# BPMLabLineRX21.net
KiCad netlist of a schematic drawn in EAGLE
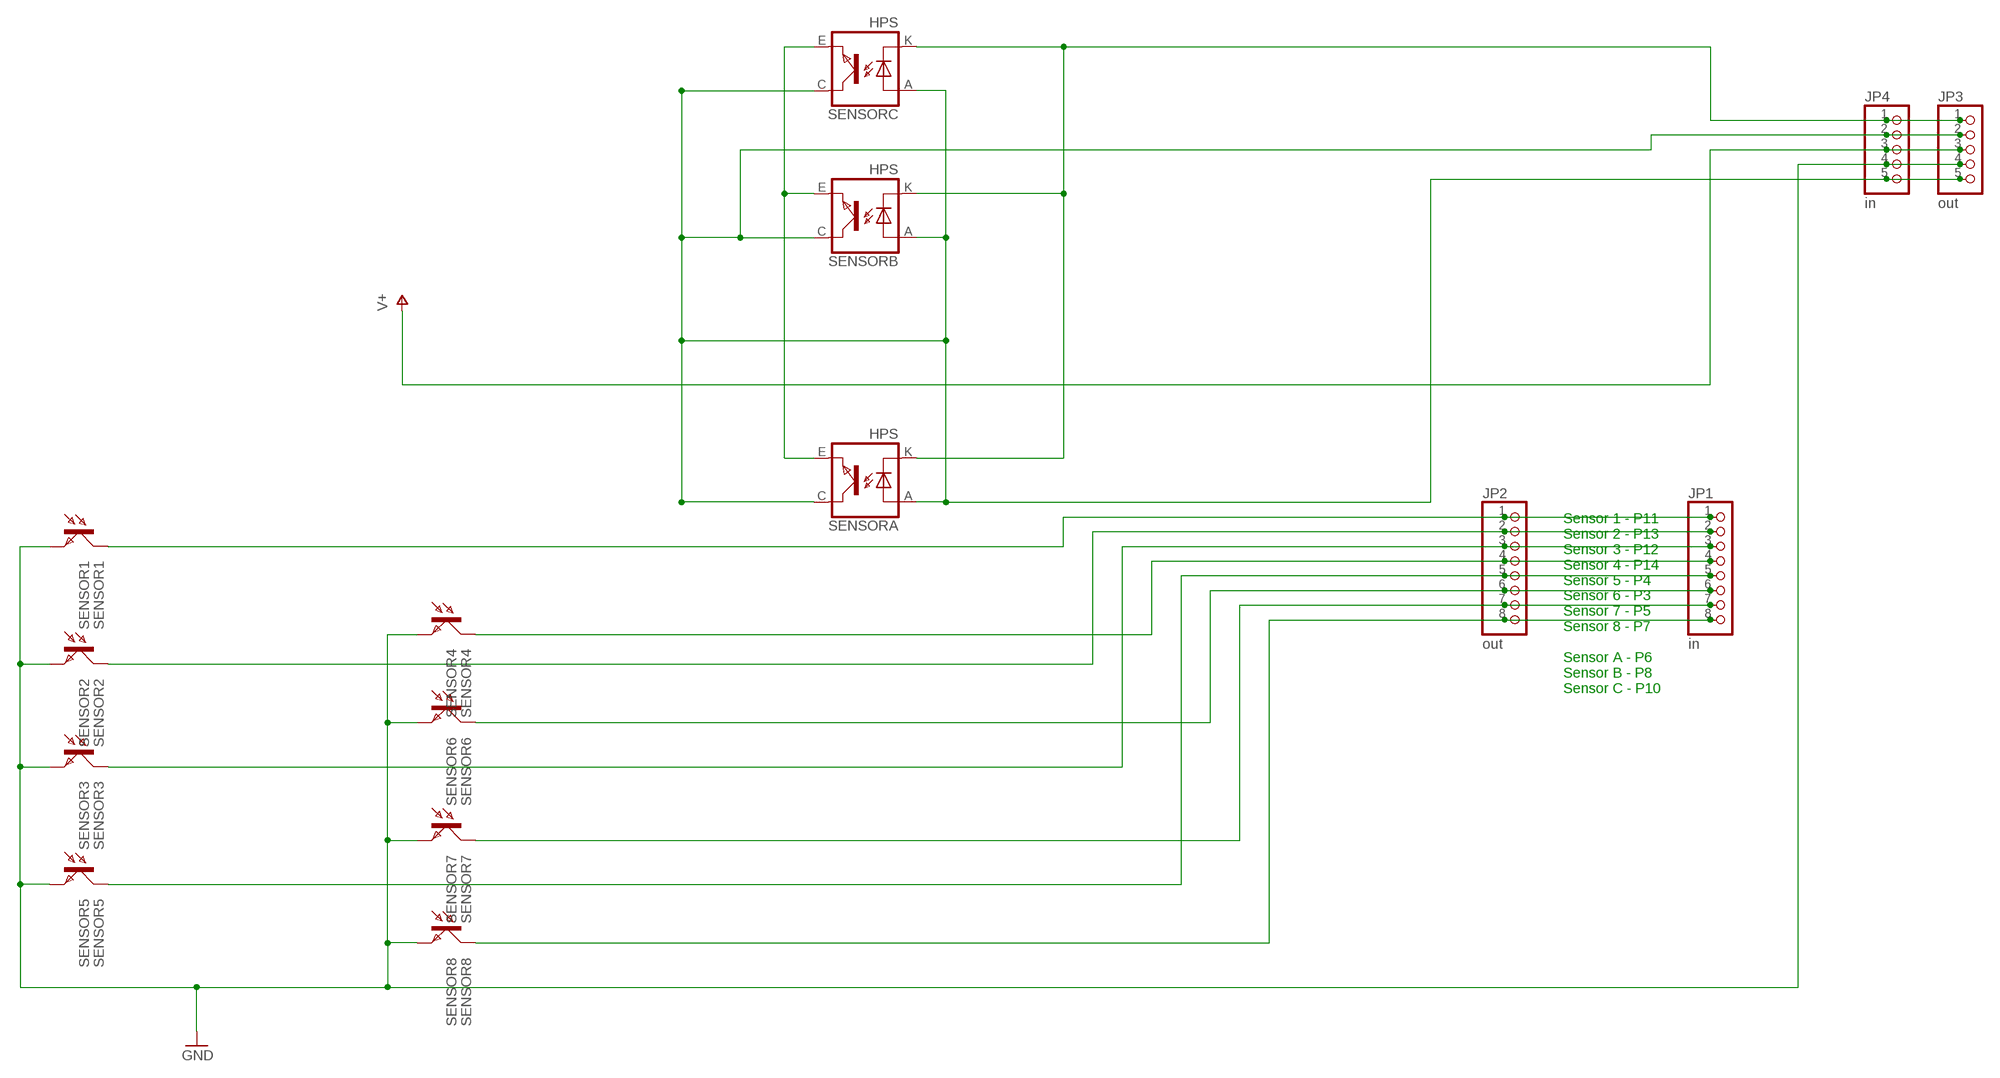
[diagram p0: schematic, sheet 1]

(export (version "E")
  (design (tool "Eeschema 10.0.6"))
  (components
    (comp (ref "JP1")
      (value "in")
      (footprint "eagle-import:1X08")
      (libsource (lib "eagle-import") (part "PINHD-1X8"))
    )
    (comp (ref "JP2")
      (value "out")
      (footprint "eagle-import:1X08")
      (libsource (lib "eagle-import") (part "PINHD-1X8"))
    )
    (comp (ref "JP3")
      (value "out")
      (footprint "eagle-import:1X05")
      (libsource (lib "eagle-import") (part "PINHD-1X5"))
    )
    (comp (ref "JP4")
      (value "in")
      (footprint "eagle-import:1X05")
      (libsource (lib "eagle-import") (part "PINHD-1X5"))
    )
    (comp (ref "SENSOR1")
      (value "SENSOR1")
      (footprint "eagle-import:BPX81")
      (libsource (lib "eagle-import") (part "BPX81"))
    )
    (comp (ref "SENSOR2")
      (value "SENSOR2")
      (footprint "eagle-import:BPX81")
      (libsource (lib "eagle-import") (part "BPX81"))
    )
    (comp (ref "SENSOR3")
      (value "SENSOR3")
      (footprint "eagle-import:BPX81")
      (libsource (lib "eagle-import") (part "BPX81"))
    )
    (comp (ref "SENSOR4")
      (value "SENSOR4")
      (footprint "eagle-import:BPX81")
      (libsource (lib "eagle-import") (part "BPX81"))
    )
    (comp (ref "SENSOR5")
      (value "SENSOR5")
      (footprint "eagle-import:BPX81")
      (libsource (lib "eagle-import") (part "BPX81"))
    )
    (comp (ref "SENSOR6")
      (value "SENSOR6")
      (footprint "eagle-import:BPX81")
      (libsource (lib "eagle-import") (part "BPX81"))
    )
    (comp (ref "SENSOR7")
      (value "SENSOR7")
      (footprint "eagle-import:BPX81")
      (libsource (lib "eagle-import") (part "BPX81"))
    )
    (comp (ref "SENSOR8")
      (value "SENSOR8")
      (footprint "eagle-import:BPX81")
      (libsource (lib "eagle-import") (part "BPX81"))
    )
    (comp (ref "SENSORA")
      (value "HPS")
      (footprint "eagle-import:TCRT5000")
      (libsource (lib "eagle-import") (part "TCRT5000"))
    )
    (comp (ref "SENSORB")
      (value "HPS")
      (footprint "eagle-import:TCRT5000")
      (libsource (lib "eagle-import") (part "TCRT5000"))
    )
    (comp (ref "SENSORC")
      (value "HPS")
      (footprint "eagle-import:TCRT5000")
      (libsource (lib "eagle-import") (part "TCRT5000"))
    )
  )
  (nets
    (net (code "1") (name "GND") (class "Default")
      (node (ref "JP3") (pin "4") (pinfunction "4_4") (pintype "passive"))
      (node (ref "JP4") (pin "4") (pinfunction "4_4") (pintype "passive"))
      (node (ref "SENSOR1") (pin "E") (pinfunction "E_E") (pintype "passive"))
      (node (ref "SENSOR2") (pin "E") (pinfunction "E_E") (pintype "passive"))
      (node (ref "SENSOR3") (pin "E") (pinfunction "E_E") (pintype "passive"))
      (node (ref "SENSOR4") (pin "E") (pinfunction "E_E") (pintype "passive"))
      (node (ref "SENSOR5") (pin "E") (pinfunction "E_E") (pintype "passive"))
      (node (ref "SENSOR6") (pin "E") (pinfunction "E_E") (pintype "passive"))
      (node (ref "SENSOR7") (pin "E") (pinfunction "E_E") (pintype "passive"))
      (node (ref "SENSOR8") (pin "E") (pinfunction "E_E") (pintype "passive"))
    )
    (net (code "2") (name "Net-(JP1-Pad1)") (class "Default")
      (node (ref "JP1") (pin "1") (pinfunction "1_1") (pintype "passive"))
      (node (ref "JP2") (pin "1") (pinfunction "1_1") (pintype "passive"))
      (node (ref "SENSOR1") (pin "C") (pinfunction "C_C") (pintype "passive"))
    )
    (net (code "3") (name "Net-(JP1-Pad2)") (class "Default")
      (node (ref "JP1") (pin "2") (pinfunction "2_2") (pintype "passive"))
      (node (ref "JP2") (pin "2") (pinfunction "2_2") (pintype "passive"))
      (node (ref "SENSOR2") (pin "C") (pinfunction "C_C") (pintype "passive"))
    )
    (net (code "4") (name "Net-(JP1-Pad3)") (class "Default")
      (node (ref "JP1") (pin "3") (pinfunction "3_3") (pintype "passive"))
      (node (ref "JP2") (pin "3") (pinfunction "3_3") (pintype "passive"))
      (node (ref "SENSOR3") (pin "C") (pinfunction "C_C") (pintype "passive"))
    )
    (net (code "5") (name "Net-(JP1-Pad4)") (class "Default")
      (node (ref "JP1") (pin "4") (pinfunction "4_4") (pintype "passive"))
      (node (ref "JP2") (pin "4") (pinfunction "4_4") (pintype "passive"))
      (node (ref "SENSOR4") (pin "C") (pinfunction "C_C") (pintype "passive"))
    )
    (net (code "6") (name "Net-(JP1-Pad5)") (class "Default")
      (node (ref "JP1") (pin "5") (pinfunction "5_5") (pintype "passive"))
      (node (ref "JP2") (pin "5") (pinfunction "5_5") (pintype "passive"))
      (node (ref "SENSOR5") (pin "C") (pinfunction "C_C") (pintype "passive"))
    )
    (net (code "7") (name "Net-(JP1-Pad6)") (class "Default")
      (node (ref "JP1") (pin "6") (pinfunction "6_6") (pintype "passive"))
      (node (ref "JP2") (pin "6") (pinfunction "6_6") (pintype "passive"))
      (node (ref "SENSOR6") (pin "C") (pinfunction "C_C") (pintype "passive"))
    )
    (net (code "8") (name "Net-(JP1-Pad7)") (class "Default")
      (node (ref "JP1") (pin "7") (pinfunction "7_7") (pintype "passive"))
      (node (ref "JP2") (pin "7") (pinfunction "7_7") (pintype "passive"))
      (node (ref "SENSOR7") (pin "C") (pinfunction "C_C") (pintype "passive"))
    )
    (net (code "9") (name "Net-(JP1-Pad8)") (class "Default")
      (node (ref "JP1") (pin "8") (pinfunction "8_8") (pintype "passive"))
      (node (ref "JP2") (pin "8") (pinfunction "8_8") (pintype "passive"))
      (node (ref "SENSOR8") (pin "C") (pinfunction "C_C") (pintype "passive"))
    )
    (net (code "10") (name "Net-(SENSORA-ANODE)") (class "Default")
      (node (ref "JP3") (pin "2") (pinfunction "2_2") (pintype "passive"))
      (node (ref "JP3") (pin "5") (pinfunction "5_5") (pintype "passive"))
      (node (ref "JP4") (pin "2") (pinfunction "2_2") (pintype "passive"))
      (node (ref "JP4") (pin "5") (pinfunction "5_5") (pintype "passive"))
      (node (ref "SENSORA") (pin "A") (pinfunction "ANODE_A") (pintype "passive"))
      (node (ref "SENSORA") (pin "C") (pinfunction "COLLECTOR_C") (pintype "passive"))
      (node (ref "SENSORB") (pin "A") (pinfunction "ANODE_A") (pintype "passive"))
      (node (ref "SENSORB") (pin "C") (pinfunction "COLLECTOR_C") (pintype "passive"))
      (node (ref "SENSORC") (pin "A") (pinfunction "ANODE_A") (pintype "passive"))
      (node (ref "SENSORC") (pin "C") (pinfunction "COLLECTOR_C") (pintype "passive"))
    )
    (net (code "11") (name "Net-(SENSORA-CATHODE)") (class "Default")
      (node (ref "JP3") (pin "1") (pinfunction "1_1") (pintype "passive"))
      (node (ref "JP4") (pin "1") (pinfunction "1_1") (pintype "passive"))
      (node (ref "SENSORA") (pin "K") (pinfunction "CATHODE_K") (pintype "passive"))
      (node (ref "SENSORB") (pin "K") (pinfunction "CATHODE_K") (pintype "passive"))
      (node (ref "SENSORC") (pin "K") (pinfunction "CATHODE_K") (pintype "passive"))
    )
    (net (code "12") (name "Net-(SENSORA-EMITTER)") (class "Default")
      (node (ref "SENSORA") (pin "E") (pinfunction "EMITTER_E") (pintype "passive"))
      (node (ref "SENSORB") (pin "E") (pinfunction "EMITTER_E") (pintype "passive"))
      (node (ref "SENSORC") (pin "E") (pinfunction "EMITTER_E") (pintype "passive"))
    )
    (net (code "13") (name "V+") (class "Default")
      (node (ref "JP3") (pin "3") (pinfunction "3_3") (pintype "passive"))
      (node (ref "JP4") (pin "3") (pinfunction "3_3") (pintype "passive"))
    )
  )
)
